# Group_08.net
KiCad netlist of a schematic drawn in EAGLE
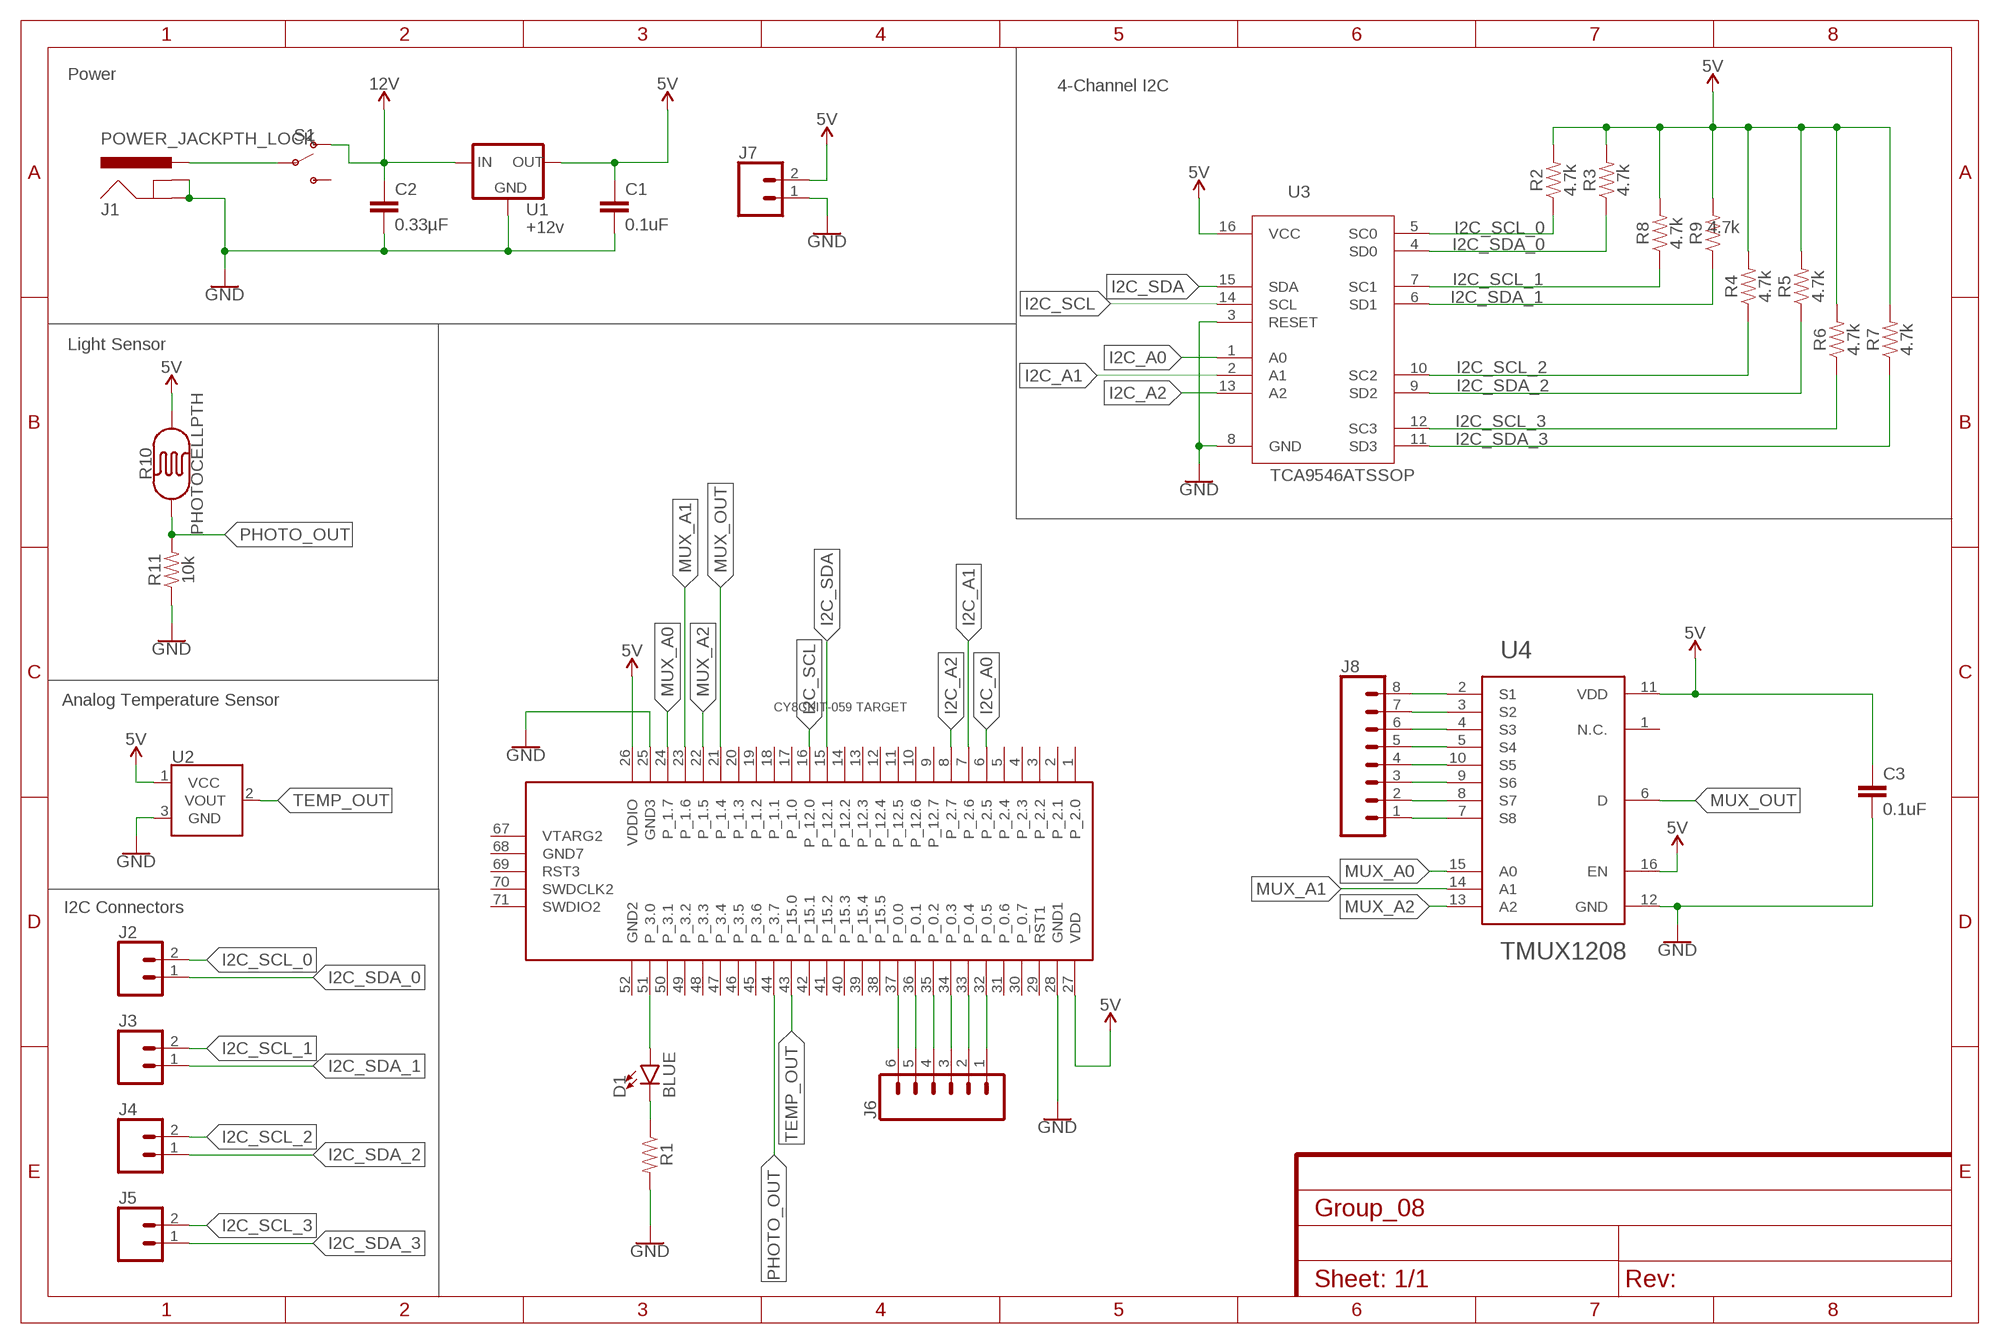
[diagram p0: schematic, sheet 1]

(export (version "E")
  (design (tool "Eeschema 10.0.6"))
  (components
    (comp (ref "C1")
      (value "0.1uF")
      (footprint "eagle-import:CAP-PTH-SMALL-KIT")
      (libsource (lib "eagle-import") (part "0.1UF-KIT-EZ-50V-20%"))
    )
    (comp (ref "C2")
      (value "0.33µF")
      (footprint "eagle-import:0805")
      (libsource (lib "eagle-import") (part "0.33UF/330NF-0805-50V-10%"))
    )
    (comp (ref "C3")
      (value "0.1uF")
      (footprint "eagle-import:CAP-PTH-SMALL-KIT")
      (libsource (lib "eagle-import") (part "0.1UF-KIT-EZ-50V-20%"))
    )
    (comp (ref "CY8CKIT059-TARGET")
      (value "CY8CKIT-059_TARGET")
      (footprint "eagle-import:CY8CKIT-059_TARGET")
      (libsource (lib "eagle-import") (part "CY8CKIT-059_TARGET"))
    )
    (comp (ref "D1")
      (value "BLUE")
      (footprint "eagle-import:LED-1206")
      (libsource (lib "eagle-import") (part "LED-BLUE1206"))
    )
    (comp (ref "J1")
      (value "POWER_JACKPTH_LOCK")
      (footprint "eagle-import:POWER_JACK_PTH_LOCK")
      (libsource (lib "eagle-import") (part "POWER_JACKPTH_LOCK"))
    )
    (comp (ref "J2")
      (value "CONN_02")
      (footprint "eagle-import:1X02")
      (libsource (lib "eagle-import") (part "CONN_02"))
    )
    (comp (ref "J3")
      (value "CONN_02")
      (footprint "eagle-import:1X02")
      (libsource (lib "eagle-import") (part "CONN_02"))
    )
    (comp (ref "J4")
      (value "CONN_02")
      (footprint "eagle-import:1X02")
      (libsource (lib "eagle-import") (part "CONN_02"))
    )
    (comp (ref "J5")
      (value "CONN_02")
      (footprint "eagle-import:1X02")
      (libsource (lib "eagle-import") (part "CONN_02"))
    )
    (comp (ref "J6")
      (value "CONN_06LOCK")
      (footprint "eagle-import:1X06_LOCK")
      (libsource (lib "eagle-import") (part "CONN_06LOCK"))
    )
    (comp (ref "J7")
      (value "CONN_02")
      (footprint "eagle-import:1X02")
      (libsource (lib "eagle-import") (part "CONN_02"))
    )
    (comp (ref "J8")
      (value "CONN_08LOCK")
      (footprint "eagle-import:1X08_LOCK")
      (libsource (lib "eagle-import") (part "CONN_08LOCK"))
    )
    (comp (ref "R1")
      (value "RESISTORAXIAL-0.3")
      (footprint "eagle-import:AXIAL-0.3")
      (libsource (lib "eagle-import") (part "RESISTORAXIAL-0.3"))
    )
    (comp (ref "R2")
      (value "4.7k")
      (footprint "eagle-import:0603")
      (libsource (lib "eagle-import") (part "4.7KOHM-0603-1/10W-1%"))
    )
    (comp (ref "R3")
      (value "4.7k")
      (footprint "eagle-import:0603")
      (libsource (lib "eagle-import") (part "4.7KOHM-0603-1/10W-1%"))
    )
    (comp (ref "R4")
      (value "4.7k")
      (footprint "eagle-import:0603")
      (libsource (lib "eagle-import") (part "4.7KOHM-0603-1/10W-1%"))
    )
    (comp (ref "R5")
      (value "4.7k")
      (footprint "eagle-import:0603")
      (libsource (lib "eagle-import") (part "4.7KOHM-0603-1/10W-1%"))
    )
    (comp (ref "R6")
      (value "4.7k")
      (footprint "eagle-import:0603")
      (libsource (lib "eagle-import") (part "4.7KOHM-0603-1/10W-1%"))
    )
    (comp (ref "R7")
      (value "4.7k")
      (footprint "eagle-import:0603")
      (libsource (lib "eagle-import") (part "4.7KOHM-0603-1/10W-1%"))
    )
    (comp (ref "R8")
      (value "4.7k")
      (footprint "eagle-import:0603")
      (libsource (lib "eagle-import") (part "4.7KOHM-0603-1/10W-1%"))
    )
    (comp (ref "R9")
      (value "4.7k")
      (footprint "eagle-import:0603")
      (libsource (lib "eagle-import") (part "4.7KOHM-0603-1/10W-1%"))
    )
    (comp (ref "R10")
      (value "PHOTOCELLPTH")
      (footprint "eagle-import:PHOTOCELL")
      (libsource (lib "eagle-import") (part "PHOTOCELLPTH"))
    )
    (comp (ref "R11")
      (value "10k")
      (footprint "eagle-import:0603")
      (libsource (lib "eagle-import") (part "10KOHM-0603-1/10W-1%"))
    )
    (comp (ref "S1")
      (value "SWITCH-SPDT-PTH-11.6X4.0MM")
      (footprint "eagle-import:SWITCH_SPDT_PTH_11.6X4.0MM")
      (libsource (lib "eagle-import") (part "SWITCH-SPDT-PTH-11.6X4.0MM"))
    )
    (comp (ref "U1")
      (value "+12v")
      (footprint "eagle-import:TO-252")
      (libsource (lib "eagle-import") (part "V_REG_78XX7812"))
    )
    (comp (ref "U2")
      (value "TMP36GT9")
      (footprint "eagle-import:TO-92")
      (libsource (lib "eagle-import") (part "TMP36GT9"))
    )
    (comp (ref "U3")
      (value "TCA9546ATSSOP")
      (footprint "eagle-import:TSSOP16")
      (libsource (lib "eagle-import") (part "TCA9546ATSSOP"))
    )
    (comp (ref "U4")
      (value "TMUX1208")
      (footprint "eagle-import:QFN16")
      (libsource (lib "eagle-import") (part "TMUX1208"))
    )
  )
  (nets
    (net (code "1") (name "5V") (class "Default")
      (node (ref "C1") (pin "1") (pinfunction "1_1") (pintype "passive"))
      (node (ref "C3") (pin "1") (pinfunction "1_1") (pintype "passive"))
      (node (ref "CY8CKIT059-TARGET") (pin "26") (pinfunction "VDDIO_26") (pintype "bidirectional"))
      (node (ref "CY8CKIT059-TARGET") (pin "27") (pinfunction "VDD_27") (pintype "bidirectional"))
      (node (ref "J7") (pin "2") (pinfunction "2_2") (pintype "passive"))
      (node (ref "R10") (pin "2") (pinfunction "P$2_2") (pintype "bidirectional"))
      (node (ref "R2") (pin "2") (pinfunction "2_2") (pintype "passive"))
      (node (ref "R3") (pin "2") (pinfunction "2_2") (pintype "passive"))
      (node (ref "R4") (pin "2") (pinfunction "2_2") (pintype "passive"))
      (node (ref "R5") (pin "2") (pinfunction "2_2") (pintype "passive"))
      (node (ref "R6") (pin "2") (pinfunction "2_2") (pintype "passive"))
      (node (ref "R7") (pin "2") (pinfunction "2_2") (pintype "passive"))
      (node (ref "R8") (pin "2") (pinfunction "2_2") (pintype "passive"))
      (node (ref "R9") (pin "2") (pinfunction "2_2") (pintype "passive"))
      (node (ref "U1") (pin "2") (pinfunction "OUT_2") (pintype "passive"))
      (node (ref "U2") (pin "1") (pinfunction "VCC_1") (pintype "bidirectional"))
      (node (ref "U3") (pin "16") (pinfunction "VCC_16") (pintype "bidirectional"))
      (node (ref "U4") (pin "11") (pinfunction "VDD_11") (pintype "bidirectional"))
      (node (ref "U4") (pin "16") (pinfunction "EN_16") (pintype "bidirectional"))
    )
    (net (code "2") (name "12V") (class "Default")
      (node (ref "C2") (pin "1") (pinfunction "1_1") (pintype "passive"))
      (node (ref "S1") (pin "1") (pinfunction "O_1") (pintype "passive"))
      (node (ref "U1") (pin "1") (pinfunction "IN_1") (pintype "input"))
    )
    (net (code "3") (name "GND") (class "Default")
      (node (ref "C1") (pin "2") (pinfunction "2_2") (pintype "passive"))
      (node (ref "C2") (pin "2") (pinfunction "2_2") (pintype "passive"))
      (node (ref "C3") (pin "2") (pinfunction "2_2") (pintype "passive"))
      (node (ref "CY8CKIT059-TARGET") (pin "25") (pinfunction "GND3_25") (pintype "bidirectional"))
      (node (ref "CY8CKIT059-TARGET") (pin "28") (pinfunction "GND1_28") (pintype "bidirectional"))
      (node (ref "J1") (pin "GND") (pinfunction "GND_GND") (pintype "bidirectional"))
      (node (ref "J1") (pin "GNDBREAK") (pinfunction "GNDBREAK_GNDBREAK") (pintype "bidirectional"))
      (node (ref "J7") (pin "1") (pinfunction "1_1") (pintype "passive"))
      (node (ref "R1") (pin "P$2") (pinfunction "2_P$2") (pintype "passive"))
      (node (ref "R11") (pin "1") (pinfunction "1_1") (pintype "passive"))
      (node (ref "U1") (pin "3") (pinfunction "GND_3") (pintype "input"))
      (node (ref "U2") (pin "3") (pinfunction "GND_3") (pintype "bidirectional"))
      (node (ref "U3") (pin "3") (pinfunction "RESET_3") (pintype "bidirectional"))
      (node (ref "U3") (pin "8") (pinfunction "GND_8") (pintype "bidirectional"))
      (node (ref "U4") (pin "12") (pinfunction "GND_12") (pintype "bidirectional"))
    )
    (net (code "4") (name "I2C_A0") (class "Default")
      (node (ref "CY8CKIT059-TARGET") (pin "6") (pinfunction "P_2.5_6") (pintype "bidirectional"))
      (node (ref "U3") (pin "1") (pinfunction "A0_1") (pintype "bidirectional"))
    )
    (net (code "5") (name "I2C_A1") (class "Default")
      (node (ref "CY8CKIT059-TARGET") (pin "7") (pinfunction "P_2.6_7") (pintype "bidirectional"))
      (node (ref "U3") (pin "2") (pinfunction "A1_2") (pintype "bidirectional"))
    )
    (net (code "6") (name "I2C_A2") (class "Default")
      (node (ref "CY8CKIT059-TARGET") (pin "8") (pinfunction "P_2.7_8") (pintype "bidirectional"))
      (node (ref "U3") (pin "13") (pinfunction "A2_13") (pintype "bidirectional"))
    )
    (net (code "7") (name "I2C_SCL") (class "Default")
      (node (ref "CY8CKIT059-TARGET") (pin "16") (pinfunction "P_12.0_16") (pintype "bidirectional"))
      (node (ref "U3") (pin "14") (pinfunction "SCL_14") (pintype "bidirectional"))
    )
    (net (code "8") (name "I2C_SCL_0") (class "Default")
      (node (ref "J2") (pin "2") (pinfunction "2_2") (pintype "passive"))
      (node (ref "R2") (pin "1") (pinfunction "1_1") (pintype "passive"))
      (node (ref "U3") (pin "5") (pinfunction "SC0_5") (pintype "bidirectional"))
    )
    (net (code "9") (name "I2C_SCL_1") (class "Default")
      (node (ref "J3") (pin "2") (pinfunction "2_2") (pintype "passive"))
      (node (ref "R8") (pin "1") (pinfunction "1_1") (pintype "passive"))
      (node (ref "U3") (pin "7") (pinfunction "SC1_7") (pintype "bidirectional"))
    )
    (net (code "10") (name "I2C_SCL_2") (class "Default")
      (node (ref "J4") (pin "2") (pinfunction "2_2") (pintype "passive"))
      (node (ref "R4") (pin "1") (pinfunction "1_1") (pintype "passive"))
      (node (ref "U3") (pin "10") (pinfunction "SC2_10") (pintype "bidirectional"))
    )
    (net (code "11") (name "I2C_SCL_3") (class "Default")
      (node (ref "J5") (pin "2") (pinfunction "2_2") (pintype "passive"))
      (node (ref "R6") (pin "1") (pinfunction "1_1") (pintype "passive"))
      (node (ref "U3") (pin "12") (pinfunction "SC3_12") (pintype "bidirectional"))
    )
    (net (code "12") (name "I2C_SDA") (class "Default")
      (node (ref "CY8CKIT059-TARGET") (pin "15") (pinfunction "P_12.1_15") (pintype "bidirectional"))
      (node (ref "U3") (pin "15") (pinfunction "SDA_15") (pintype "bidirectional"))
    )
    (net (code "13") (name "I2C_SDA_0") (class "Default")
      (node (ref "J2") (pin "1") (pinfunction "1_1") (pintype "passive"))
      (node (ref "R3") (pin "1") (pinfunction "1_1") (pintype "passive"))
      (node (ref "U3") (pin "4") (pinfunction "SD0_4") (pintype "bidirectional"))
    )
    (net (code "14") (name "I2C_SDA_1") (class "Default")
      (node (ref "J3") (pin "1") (pinfunction "1_1") (pintype "passive"))
      (node (ref "R9") (pin "1") (pinfunction "1_1") (pintype "passive"))
      (node (ref "U3") (pin "6") (pinfunction "SD1_6") (pintype "bidirectional"))
    )
    (net (code "15") (name "I2C_SDA_2") (class "Default")
      (node (ref "J4") (pin "1") (pinfunction "1_1") (pintype "passive"))
      (node (ref "R5") (pin "1") (pinfunction "1_1") (pintype "passive"))
      (node (ref "U3") (pin "9") (pinfunction "SD2_9") (pintype "bidirectional"))
    )
    (net (code "16") (name "I2C_SDA_3") (class "Default")
      (node (ref "J5") (pin "1") (pinfunction "1_1") (pintype "passive"))
      (node (ref "R7") (pin "1") (pinfunction "1_1") (pintype "passive"))
      (node (ref "U3") (pin "11") (pinfunction "SD3_11") (pintype "bidirectional"))
    )
    (net (code "17") (name "MUX_A0") (class "Default")
      (node (ref "CY8CKIT059-TARGET") (pin "24") (pinfunction "P_1.7_24") (pintype "bidirectional"))
      (node (ref "U4") (pin "15") (pinfunction "A0_15") (pintype "bidirectional"))
    )
    (net (code "18") (name "MUX_A1") (class "Default")
      (node (ref "CY8CKIT059-TARGET") (pin "23") (pinfunction "P_1.6_23") (pintype "bidirectional"))
      (node (ref "U4") (pin "14") (pinfunction "A1_14") (pintype "bidirectional"))
    )
    (net (code "19") (name "MUX_A2") (class "Default")
      (node (ref "CY8CKIT059-TARGET") (pin "22") (pinfunction "P_1.5_22") (pintype "bidirectional"))
      (node (ref "U4") (pin "13") (pinfunction "A2_13") (pintype "bidirectional"))
    )
    (net (code "20") (name "MUX_OUT") (class "Default")
      (node (ref "CY8CKIT059-TARGET") (pin "21") (pinfunction "P_1.4_21") (pintype "bidirectional"))
      (node (ref "U4") (pin "6") (pinfunction "D_6") (pintype "bidirectional"))
    )
    (net (code "21") (name "Net-(CY8CKIT059-TARGET-P_0.0)") (class "Default")
      (node (ref "CY8CKIT059-TARGET") (pin "37") (pinfunction "P_0.0_37") (pintype "bidirectional"))
      (node (ref "J6") (pin "6") (pinfunction "6_6") (pintype "passive"))
    )
    (net (code "22") (name "Net-(CY8CKIT059-TARGET-P_0.1)") (class "Default")
      (node (ref "CY8CKIT059-TARGET") (pin "36") (pinfunction "P_0.1_36") (pintype "bidirectional"))
      (node (ref "J6") (pin "5") (pinfunction "5_5") (pintype "passive"))
    )
    (net (code "23") (name "Net-(CY8CKIT059-TARGET-P_0.2)") (class "Default")
      (node (ref "CY8CKIT059-TARGET") (pin "35") (pinfunction "P_0.2_35") (pintype "bidirectional"))
      (node (ref "J6") (pin "4") (pinfunction "4_4") (pintype "passive"))
    )
    (net (code "24") (name "Net-(CY8CKIT059-TARGET-P_0.3)") (class "Default")
      (node (ref "CY8CKIT059-TARGET") (pin "34") (pinfunction "P_0.3_34") (pintype "bidirectional"))
      (node (ref "J6") (pin "3") (pinfunction "3_3") (pintype "passive"))
    )
    (net (code "25") (name "Net-(CY8CKIT059-TARGET-P_0.4)") (class "Default")
      (node (ref "CY8CKIT059-TARGET") (pin "33") (pinfunction "P_0.4_33") (pintype "bidirectional"))
      (node (ref "J6") (pin "2") (pinfunction "2_2") (pintype "passive"))
    )
    (net (code "26") (name "Net-(CY8CKIT059-TARGET-P_0.5)") (class "Default")
      (node (ref "CY8CKIT059-TARGET") (pin "32") (pinfunction "P_0.5_32") (pintype "bidirectional"))
      (node (ref "J6") (pin "1") (pinfunction "1_1") (pintype "passive"))
    )
    (net (code "27") (name "Net-(CY8CKIT059-TARGET-P_3.0)") (class "Default")
      (node (ref "CY8CKIT059-TARGET") (pin "51") (pinfunction "P_3.0_51") (pintype "bidirectional"))
      (node (ref "D1") (pin "A") (pinfunction "A_A") (pintype "passive"))
    )
    (net (code "28") (name "Net-(R1-1)") (class "Default")
      (node (ref "D1") (pin "C") (pinfunction "C_C") (pintype "passive"))
      (node (ref "R1") (pin "P$1") (pinfunction "1_P$1") (pintype "passive"))
    )
    (net (code "29") (name "Net-(S1-P)") (class "Default")
      (node (ref "J1") (pin "PWR") (pinfunction "PWR_PWR") (pintype "bidirectional"))
      (node (ref "S1") (pin "2") (pinfunction "P_2") (pintype "passive"))
    )
    (net (code "30") (name "Net-(U4-S1)") (class "Default")
      (node (ref "J8") (pin "8") (pinfunction "8_8") (pintype "passive"))
      (node (ref "U4") (pin "2") (pinfunction "S1_2") (pintype "bidirectional"))
    )
    (net (code "31") (name "Net-(U4-S2)") (class "Default")
      (node (ref "J8") (pin "7") (pinfunction "7_7") (pintype "passive"))
      (node (ref "U4") (pin "3") (pinfunction "S2_3") (pintype "bidirectional"))
    )
    (net (code "32") (name "Net-(U4-S3)") (class "Default")
      (node (ref "J8") (pin "6") (pinfunction "6_6") (pintype "passive"))
      (node (ref "U4") (pin "4") (pinfunction "S3_4") (pintype "bidirectional"))
    )
    (net (code "33") (name "Net-(U4-S4)") (class "Default")
      (node (ref "J8") (pin "5") (pinfunction "5_5") (pintype "passive"))
      (node (ref "U4") (pin "5") (pinfunction "S4_5") (pintype "bidirectional"))
    )
    (net (code "34") (name "Net-(U4-S5)") (class "Default")
      (node (ref "J8") (pin "4") (pinfunction "4_4") (pintype "passive"))
      (node (ref "U4") (pin "10") (pinfunction "S5_10") (pintype "bidirectional"))
    )
    (net (code "35") (name "Net-(U4-S6)") (class "Default")
      (node (ref "J8") (pin "3") (pinfunction "3_3") (pintype "passive"))
      (node (ref "U4") (pin "9") (pinfunction "S6_9") (pintype "bidirectional"))
    )
    (net (code "36") (name "Net-(U4-S7)") (class "Default")
      (node (ref "J8") (pin "2") (pinfunction "2_2") (pintype "passive"))
      (node (ref "U4") (pin "8") (pinfunction "S7_8") (pintype "bidirectional"))
    )
    (net (code "37") (name "Net-(U4-S8)") (class "Default")
      (node (ref "J8") (pin "1") (pinfunction "1_1") (pintype "passive"))
      (node (ref "U4") (pin "7") (pinfunction "S8_7") (pintype "bidirectional"))
    )
    (net (code "38") (name "PHOTO_OUT") (class "Default")
      (node (ref "CY8CKIT059-TARGET") (pin "44") (pinfunction "P_3.7_44") (pintype "bidirectional"))
      (node (ref "R10") (pin "1") (pinfunction "P$1_1") (pintype "bidirectional"))
      (node (ref "R11") (pin "2") (pinfunction "2_2") (pintype "passive"))
    )
    (net (code "39") (name "TEMP_OUT") (class "Default")
      (node (ref "CY8CKIT059-TARGET") (pin "43") (pinfunction "P_15.0_43") (pintype "bidirectional"))
      (node (ref "U2") (pin "2") (pinfunction "VOUT_2") (pintype "bidirectional"))
    )
    (net (code "40") (name "unconnected-(CY8CKIT059-TARGET-GND2-Pad52)") (class "Default")
      (node (ref "CY8CKIT059-TARGET") (pin "52") (pinfunction "GND2_52") (pintype "bidirectional"))
    )
    (net (code "41") (name "unconnected-(CY8CKIT059-TARGET-GND7-Pad68)") (class "Default")
      (node (ref "CY8CKIT059-TARGET") (pin "68") (pinfunction "GND7_68") (pintype "bidirectional"))
    )
    (net (code "42") (name "unconnected-(CY8CKIT059-TARGET-P_0.6-Pad31)") (class "Default")
      (node (ref "CY8CKIT059-TARGET") (pin "31") (pinfunction "P_0.6_31") (pintype "bidirectional"))
    )
    (net (code "43") (name "unconnected-(CY8CKIT059-TARGET-P_0.7-Pad30)") (class "Default")
      (node (ref "CY8CKIT059-TARGET") (pin "30") (pinfunction "P_0.7_30") (pintype "bidirectional"))
    )
    (net (code "44") (name "unconnected-(CY8CKIT059-TARGET-P_1.0-Pad17)") (class "Default")
      (node (ref "CY8CKIT059-TARGET") (pin "17") (pinfunction "P_1.0_17") (pintype "bidirectional"))
    )
    (net (code "45") (name "unconnected-(CY8CKIT059-TARGET-P_1.1-Pad18)") (class "Default")
      (node (ref "CY8CKIT059-TARGET") (pin "18") (pinfunction "P_1.1_18") (pintype "bidirectional"))
    )
    (net (code "46") (name "unconnected-(CY8CKIT059-TARGET-P_1.2-Pad19)") (class "Default")
      (node (ref "CY8CKIT059-TARGET") (pin "19") (pinfunction "P_1.2_19") (pintype "bidirectional"))
    )
    (net (code "47") (name "unconnected-(CY8CKIT059-TARGET-P_1.3-Pad20)") (class "Default")
      (node (ref "CY8CKIT059-TARGET") (pin "20") (pinfunction "P_1.3_20") (pintype "bidirectional"))
    )
    (net (code "48") (name "unconnected-(CY8CKIT059-TARGET-P_2.0-Pad1)") (class "Default")
      (node (ref "CY8CKIT059-TARGET") (pin "1") (pinfunction "P_2.0_1") (pintype "bidirectional"))
    )
    (net (code "49") (name "unconnected-(CY8CKIT059-TARGET-P_2.1-Pad2)") (class "Default")
      (node (ref "CY8CKIT059-TARGET") (pin "2") (pinfunction "P_2.1_2") (pintype "bidirectional"))
    )
    (net (code "50") (name "unconnected-(CY8CKIT059-TARGET-P_2.2-Pad3)") (class "Default")
      (node (ref "CY8CKIT059-TARGET") (pin "3") (pinfunction "P_2.2_3") (pintype "bidirectional"))
    )
    (net (code "51") (name "unconnected-(CY8CKIT059-TARGET-P_2.3-Pad4)") (class "Default")
      (node (ref "CY8CKIT059-TARGET") (pin "4") (pinfunction "P_2.3_4") (pintype "bidirectional"))
    )
    (net (code "52") (name "unconnected-(CY8CKIT059-TARGET-P_2.4-Pad5)") (class "Default")
      (node (ref "CY8CKIT059-TARGET") (pin "5") (pinfunction "P_2.4_5") (pintype "bidirectional"))
    )
    (net (code "53") (name "unconnected-(CY8CKIT059-TARGET-P_3.1-Pad50)") (class "Default")
      (node (ref "CY8CKIT059-TARGET") (pin "50") (pinfunction "P_3.1_50") (pintype "bidirectional"))
    )
    (net (code "54") (name "unconnected-(CY8CKIT059-TARGET-P_3.2-Pad49)") (class "Default")
      (node (ref "CY8CKIT059-TARGET") (pin "49") (pinfunction "P_3.2_49") (pintype "bidirectional"))
    )
    (net (code "55") (name "unconnected-(CY8CKIT059-TARGET-P_3.3-Pad48)") (class "Default")
      (node (ref "CY8CKIT059-TARGET") (pin "48") (pinfunction "P_3.3_48") (pintype "bidirectional"))
    )
    (net (code "56") (name "unconnected-(CY8CKIT059-TARGET-P_3.4-Pad47)") (class "Default")
      (node (ref "CY8CKIT059-TARGET") (pin "47") (pinfunction "P_3.4_47") (pintype "bidirectional"))
    )
    (net (code "57") (name "unconnected-(CY8CKIT059-TARGET-P_3.5-Pad46)") (class "Default")
      (node (ref "CY8CKIT059-TARGET") (pin "46") (pinfunction "P_3.5_46") (pintype "bidirectional"))
    )
    (net (code "58") (name "unconnected-(CY8CKIT059-TARGET-P_3.6-Pad45)") (class "Default")
      (node (ref "CY8CKIT059-TARGET") (pin "45") (pinfunction "P_3.6_45") (pintype "bidirectional"))
    )
    (net (code "59") (name "unconnected-(CY8CKIT059-TARGET-P_12.2-Pad14)") (class "Default")
      (node (ref "CY8CKIT059-TARGET") (pin "14") (pinfunction "P_12.2_14") (pintype "bidirectional"))
    )
    (net (code "60") (name "unconnected-(CY8CKIT059-TARGET-P_12.3-Pad13)") (class "Default")
      (node (ref "CY8CKIT059-TARGET") (pin "13") (pinfunction "P_12.3_13") (pintype "bidirectional"))
    )
    (net (code "61") (name "unconnected-(CY8CKIT059-TARGET-P_12.4-Pad12)") (class "Default")
      (node (ref "CY8CKIT059-TARGET") (pin "12") (pinfunction "P_12.4_12") (pintype "bidirectional"))
    )
    (net (code "62") (name "unconnected-(CY8CKIT059-TARGET-P_12.5-Pad11)") (class "Default")
      (node (ref "CY8CKIT059-TARGET") (pin "11") (pinfunction "P_12.5_11") (pintype "bidirectional"))
    )
    (net (code "63") (name "unconnected-(CY8CKIT059-TARGET-P_12.6-Pad10)") (class "Default")
      (node (ref "CY8CKIT059-TARGET") (pin "10") (pinfunction "P_12.6_10") (pintype "bidirectional"))
    )
    (net (code "64") (name "unconnected-(CY8CKIT059-TARGET-P_12.7-Pad9)") (class "Default")
      (node (ref "CY8CKIT059-TARGET") (pin "9") (pinfunction "P_12.7_9") (pintype "bidirectional"))
    )
    (net (code "65") (name "unconnected-(CY8CKIT059-TARGET-P_15.1-Pad42)") (class "Default")
      (node (ref "CY8CKIT059-TARGET") (pin "42") (pinfunction "P_15.1_42") (pintype "bidirectional"))
    )
    (net (code "66") (name "unconnected-(CY8CKIT059-TARGET-P_15.2-Pad41)") (class "Default")
      (node (ref "CY8CKIT059-TARGET") (pin "41") (pinfunction "P_15.2_41") (pintype "bidirectional"))
    )
    (net (code "67") (name "unconnected-(CY8CKIT059-TARGET-P_15.3-Pad40)") (class "Default")
      (node (ref "CY8CKIT059-TARGET") (pin "40") (pinfunction "P_15.3_40") (pintype "bidirectional"))
    )
    (net (code "68") (name "unconnected-(CY8CKIT059-TARGET-P_15.4-Pad39)") (class "Default")
      (node (ref "CY8CKIT059-TARGET") (pin "39") (pinfunction "P_15.4_39") (pintype "bidirectional"))
    )
    (net (code "69") (name "unconnected-(CY8CKIT059-TARGET-P_15.5-Pad38)") (class "Default")
      (node (ref "CY8CKIT059-TARGET") (pin "38") (pinfunction "P_15.5_38") (pintype "bidirectional"))
    )
    (net (code "70") (name "unconnected-(CY8CKIT059-TARGET-RST1-Pad29)") (class "Default")
      (node (ref "CY8CKIT059-TARGET") (pin "29") (pinfunction "RST1_29") (pintype "bidirectional"))
    )
    (net (code "71") (name "unconnected-(CY8CKIT059-TARGET-RST3-Pad69)") (class "Default")
      (node (ref "CY8CKIT059-TARGET") (pin "69") (pinfunction "RST3_69") (pintype "bidirectional"))
    )
    (net (code "72") (name "unconnected-(CY8CKIT059-TARGET-SWDCLK2-Pad70)") (class "Default")
      (node (ref "CY8CKIT059-TARGET") (pin "70") (pinfunction "SWDCLK2_70") (pintype "bidirectional"))
    )
    (net (code "73") (name "unconnected-(CY8CKIT059-TARGET-SWDIO2-Pad71)") (class "Default")
      (node (ref "CY8CKIT059-TARGET") (pin "71") (pinfunction "SWDIO2_71") (pintype "bidirectional"))
    )
    (net (code "74") (name "unconnected-(CY8CKIT059-TARGET-VTARG2-Pad67)") (class "Default")
      (node (ref "CY8CKIT059-TARGET") (pin "67") (pinfunction "VTARG2_67") (pintype "bidirectional"))
    )
    (net (code "75") (name "unconnected-(S1-S-Pad3)") (class "Default")
      (node (ref "S1") (pin "3") (pinfunction "S_3") (pintype "passive"))
    )
    (net (code "76") (name "unconnected-(U4-N.C.-Pad1)") (class "Default")
      (node (ref "U4") (pin "1") (pinfunction "N.C._1") (pintype "bidirectional"))
    )
  )
)
